# SCH_UD-05-PCB-design-Lucas-Perello_2025-.net
KiCad netlist of a schematic drawn in EasyEDA
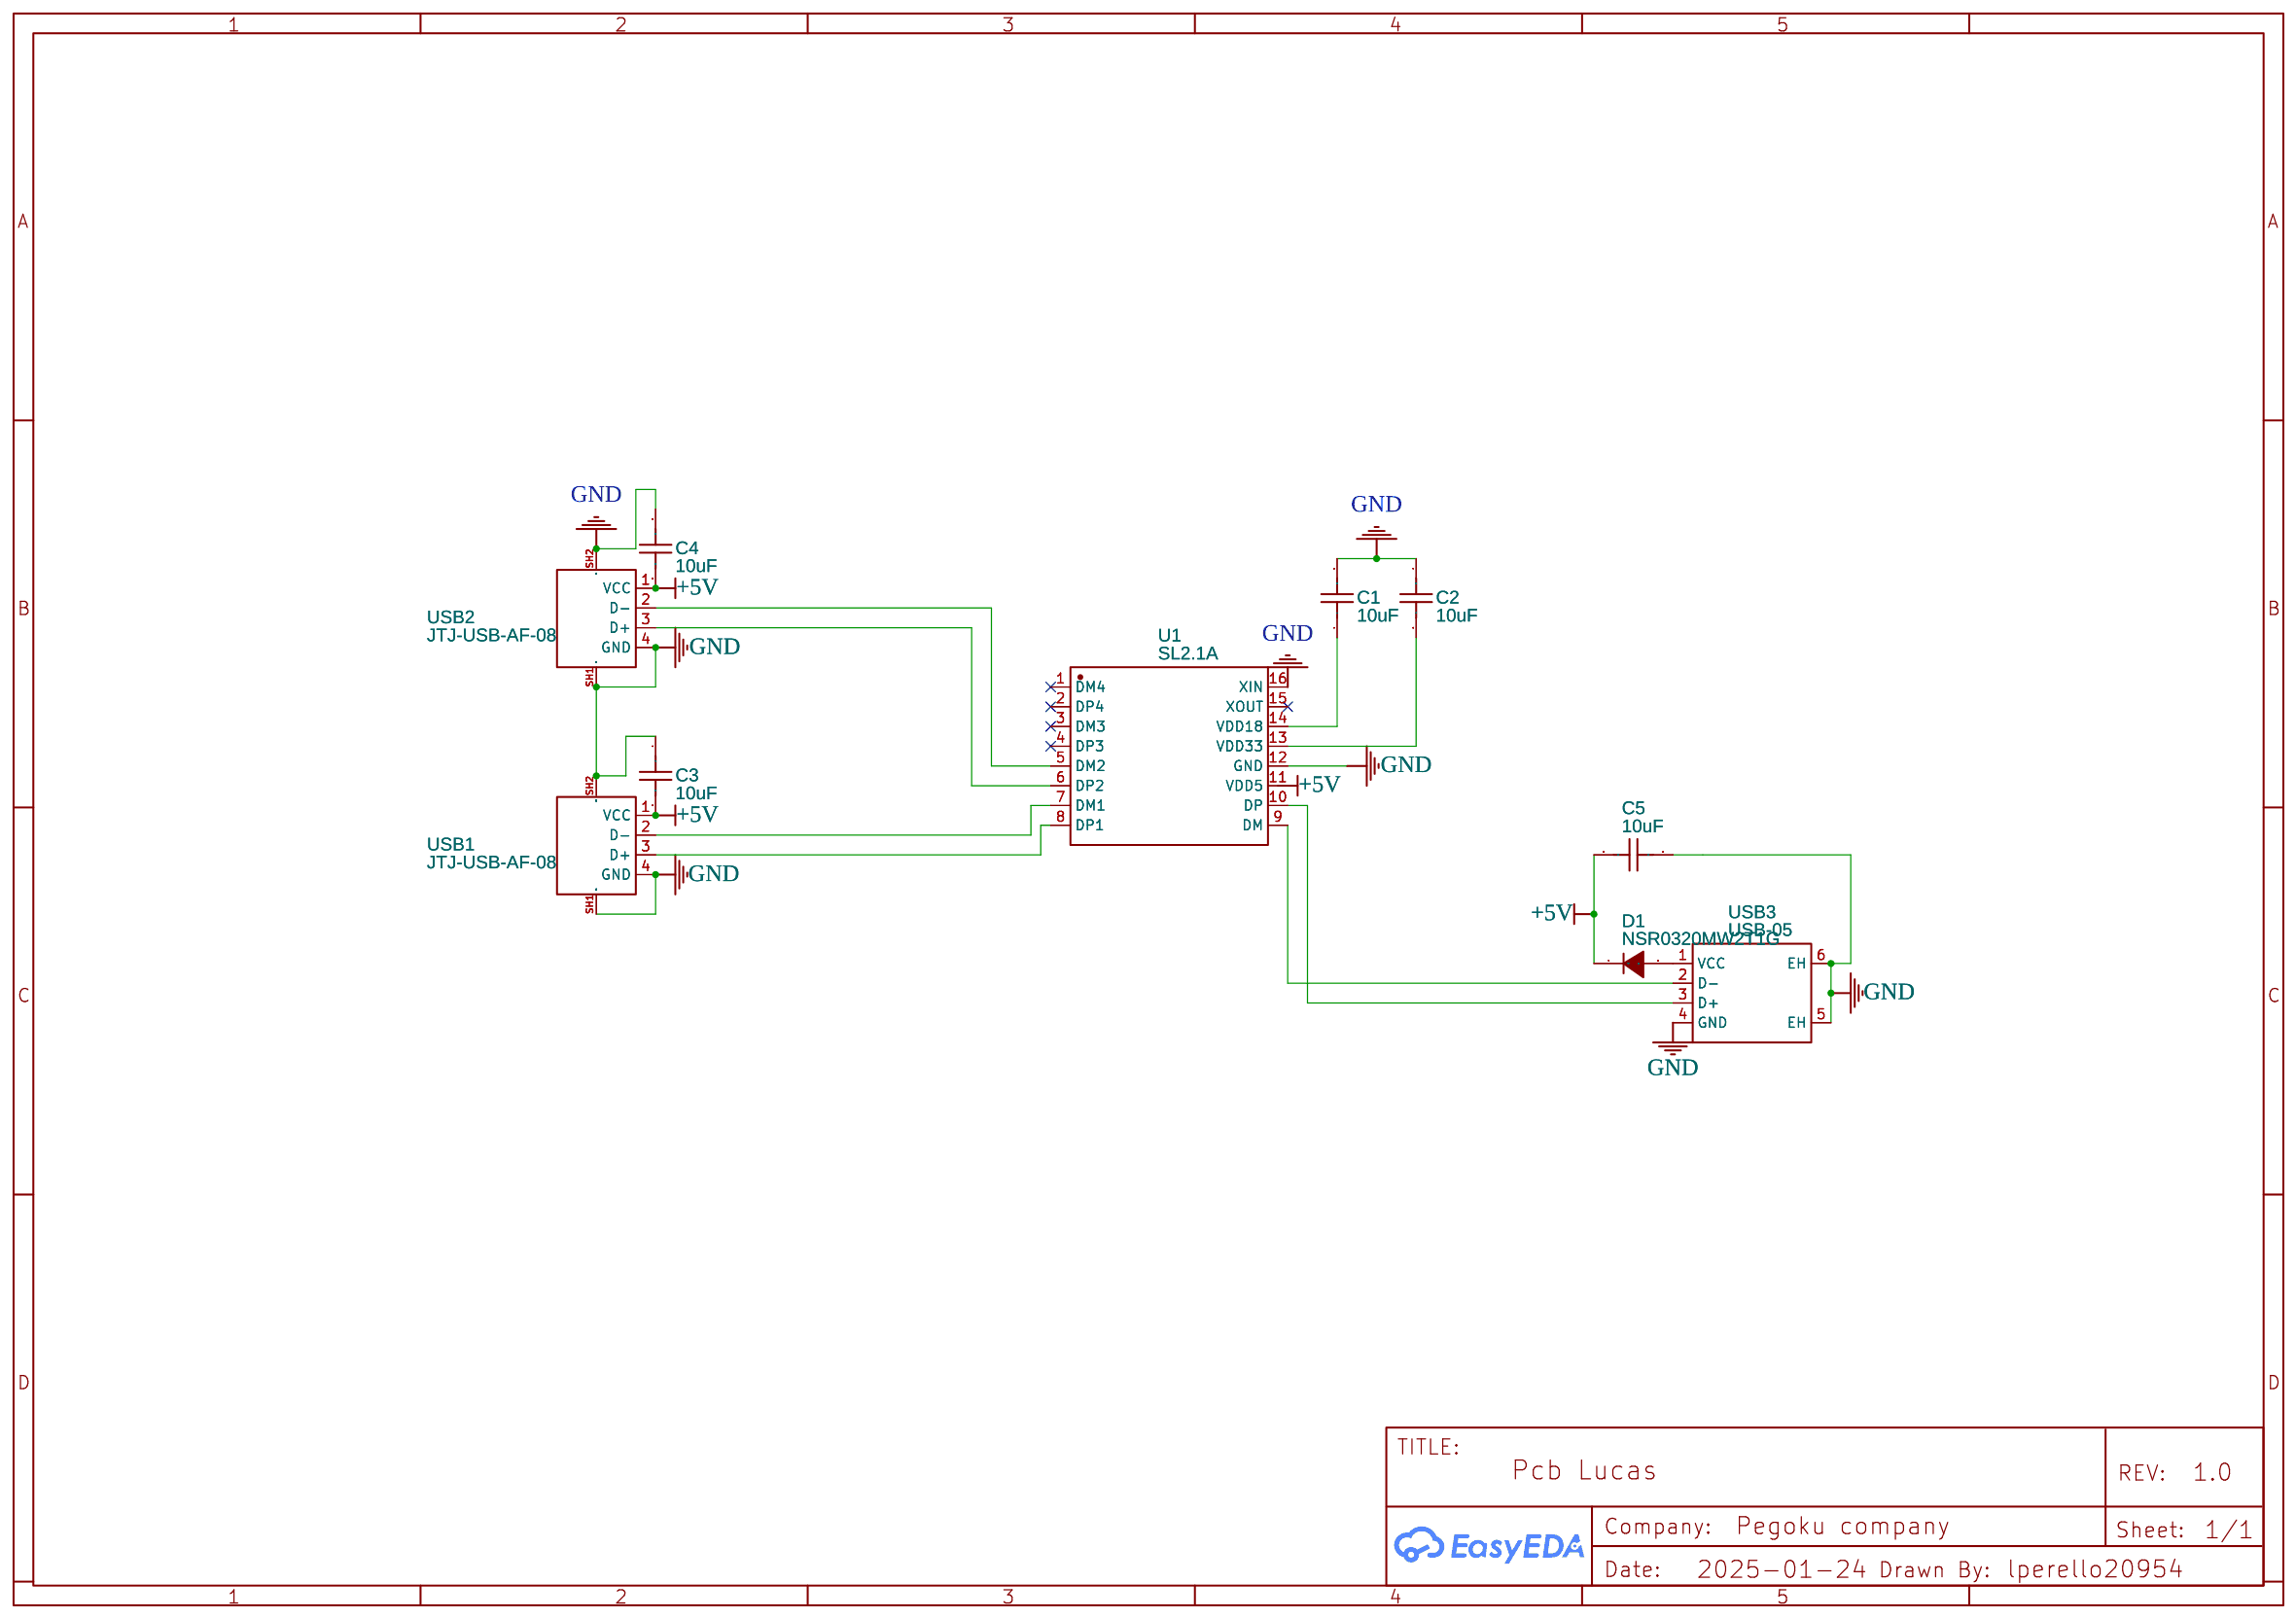
[diagram p0: schematic sheet]

(export (version "E")
  (design (tool "Eeschema 10.0.6"))
  (components
    (comp (ref "C1")
      (value "10uF")
      (fields
        (field (name "Manufacturer Part") "CL10A106KP8NNNC")
        (field (name "Manufacturer") "SAMSUNG(三星)")
      )
      (libsource (lib "") (part "CL10A106KP8NNNC"))
    )
    (comp (ref "C2")
      (value "10uF")
      (fields
        (field (name "Manufacturer Part") "CL10A106KP8NNNC")
        (field (name "Manufacturer") "SAMSUNG(三星)")
      )
      (libsource (lib "") (part "CL10A106KP8NNNC_1"))
    )
    (comp (ref "C3")
      (value "10uF")
      (fields
        (field (name "Manufacturer Part") "CL10A106KP8NNNC")
        (field (name "Manufacturer") "SAMSUNG(三星)")
      )
      (libsource (lib "") (part "CL10A106KP8NNNC_1"))
    )
    (comp (ref "C4")
      (value "10uF")
      (fields
        (field (name "Manufacturer Part") "CL10A106KP8NNNC")
        (field (name "Manufacturer") "SAMSUNG(三星)")
      )
      (libsource (lib "") (part "CL10A106KP8NNNC_1"))
    )
    (comp (ref "C5")
      (value "10uF")
      (fields
        (field (name "Manufacturer Part") "CL10A106KP8NNNC")
        (field (name "Manufacturer") "SAMSUNG(三星)")
      )
      (libsource (lib "") (part "CL10A106KP8NNNC_2"))
    )
    (comp (ref "D1")
      (value "NSR0320MW2T1G")
      (fields (field (name "Manufacturer") "onsemi(安森美)"))
      (libsource (lib "") (part "NSR0320MW2T1G"))
    )
    (comp (ref "U1")
      (value "SL2.1A")
      (fields (field (name "Manufacturer") "CoreChips(和芯润德)"))
      (libsource (lib "") (part "SL2.1A"))
    )
    (comp (ref "USB1")
      (value "JTJ-USB-AF-08")
      (fields (field (name "Manufacturer Part") "902-131A1011D10100") (field (name "Manufacturer") "精拓金"))
      (libsource (lib "") (part "JTJ-USB-AF-08"))
    )
    (comp (ref "USB2")
      (value "JTJ-USB-AF-08")
      (fields (field (name "Manufacturer Part") "902-131A1011D10100") (field (name "Manufacturer") "精拓金"))
      (libsource (lib "") (part "JTJ-USB-AF-08"))
    )
    (comp (ref "USB3")
      (value "USB-05")
      (fields (field (name "Manufacturer") "SOFNG(硕方)"))
      (libsource (lib "") (part "USB-05"))
    )
  )
  (nets
    (net (code "1") (name "+5V") (class "Default")
      (node (ref "C3") (pin "2") (pinfunction "2_2") (pintype "unspecified"))
      (node (ref "C4") (pin "2") (pinfunction "2_2") (pintype "unspecified"))
      (node (ref "C5") (pin "2") (pinfunction "2_2") (pintype "unspecified"))
      (node (ref "D1") (pin "1") (pinfunction "C_1") (pintype "unspecified"))
      (node (ref "U1") (pin "11") (pinfunction "VDD5_11") (pintype "unspecified"))
      (node (ref "USB1") (pin "1") (pinfunction "VCC_1") (pintype "input"))
      (node (ref "USB2") (pin "1") (pinfunction "VCC_1") (pintype "input"))
    )
    (net (code "2") (name "GND") (class "Default")
      (node (ref "C1") (pin "2") (pinfunction "2_2") (pintype "unspecified"))
      (node (ref "C2") (pin "1") (pinfunction "1_1") (pintype "unspecified"))
      (node (ref "C3") (pin "1") (pinfunction "1_1") (pintype "unspecified"))
      (node (ref "C4") (pin "1") (pinfunction "1_1") (pintype "unspecified"))
      (node (ref "C5") (pin "1") (pinfunction "1_1") (pintype "unspecified"))
      (node (ref "U1") (pin "12") (pinfunction "GND_12") (pintype "unspecified"))
      (node (ref "U1") (pin "16") (pinfunction "XIN_16") (pintype "unspecified"))
      (node (ref "USB1") (pin "4") (pinfunction "GND_4") (pintype "input"))
      (node (ref "USB1") (pin "SH1") (pinfunction "SH1_SH1") (pintype "unspecified"))
      (node (ref "USB1") (pin "SH2") (pinfunction "SH2_SH2") (pintype "unspecified"))
      (node (ref "USB2") (pin "4") (pinfunction "GND_4") (pintype "input"))
      (node (ref "USB2") (pin "SH1") (pinfunction "SH1_SH1") (pintype "unspecified"))
      (node (ref "USB2") (pin "SH2") (pinfunction "SH2_SH2") (pintype "unspecified"))
      (node (ref "USB3") (pin "4") (pinfunction "GND_4") (pintype "input"))
      (node (ref "USB3") (pin "5") (pinfunction "EH_5") (pintype "unspecified"))
      (node (ref "USB3") (pin "6") (pinfunction "EH_6") (pintype "unspecified"))
    )
    (net (code "3") (name "Net-(D1-A)") (class "Default")
      (node (ref "D1") (pin "2") (pinfunction "A_2") (pintype "unspecified"))
      (node (ref "USB3") (pin "1") (pinfunction "VCC_1") (pintype "input"))
    )
    (net (code "4") (name "Net-(U1-DM)") (class "Default")
      (node (ref "U1") (pin "9") (pinfunction "DM_9") (pintype "unspecified"))
      (node (ref "USB3") (pin "2") (pinfunction "D-_2") (pintype "input"))
    )
    (net (code "5") (name "Net-(U1-DM1)") (class "Default")
      (node (ref "U1") (pin "7") (pinfunction "DM1_7") (pintype "unspecified"))
      (node (ref "USB1") (pin "2") (pinfunction "D-_2") (pintype "input"))
    )
    (net (code "6") (name "Net-(U1-DM2)") (class "Default")
      (node (ref "U1") (pin "5") (pinfunction "DM2_5") (pintype "unspecified"))
      (node (ref "USB2") (pin "2") (pinfunction "D-_2") (pintype "input"))
    )
    (net (code "7") (name "Net-(U1-DP)") (class "Default")
      (node (ref "U1") (pin "10") (pinfunction "DP_10") (pintype "unspecified"))
      (node (ref "USB3") (pin "3") (pinfunction "D+_3") (pintype "input"))
    )
    (net (code "8") (name "Net-(U1-DP1)") (class "Default")
      (node (ref "U1") (pin "8") (pinfunction "DP1_8") (pintype "unspecified"))
      (node (ref "USB1") (pin "3") (pinfunction "D+_3") (pintype "input"))
    )
    (net (code "9") (name "Net-(U1-DP2)") (class "Default")
      (node (ref "U1") (pin "6") (pinfunction "DP2_6") (pintype "unspecified"))
      (node (ref "USB2") (pin "3") (pinfunction "D+_3") (pintype "input"))
    )
    (net (code "10") (name "Net-(U1-VDD18)") (class "Default")
      (node (ref "C1") (pin "1") (pinfunction "1_1") (pintype "unspecified"))
      (node (ref "U1") (pin "14") (pinfunction "VDD18_14") (pintype "unspecified"))
    )
    (net (code "11") (name "Net-(U1-VDD33)") (class "Default")
      (node (ref "C2") (pin "2") (pinfunction "2_2") (pintype "unspecified"))
      (node (ref "U1") (pin "13") (pinfunction "VDD33_13") (pintype "unspecified"))
    )
    (net (code "12") (name "unconnected-(U1-DM3-Pad3)") (class "Default")
      (node (ref "U1") (pin "3") (pinfunction "DM3_3") (pintype "unspecified+no_connect"))
    )
    (net (code "13") (name "unconnected-(U1-DM4-Pad1)") (class "Default")
      (node (ref "U1") (pin "1") (pinfunction "DM4_1") (pintype "unspecified+no_connect"))
    )
    (net (code "14") (name "unconnected-(U1-DP3-Pad4)") (class "Default")
      (node (ref "U1") (pin "4") (pinfunction "DP3_4") (pintype "unspecified+no_connect"))
    )
    (net (code "15") (name "unconnected-(U1-DP4-Pad2)") (class "Default")
      (node (ref "U1") (pin "2") (pinfunction "DP4_2") (pintype "unspecified+no_connect"))
    )
    (net (code "16") (name "unconnected-(U1-XOUT-Pad15)") (class "Default")
      (node (ref "U1") (pin "15") (pinfunction "XOUT_15") (pintype "unspecified+no_connect"))
    )
  )
)
